# CC_Led_Driver.net
KiCad netlist of a schematic drawn in Altium Designer
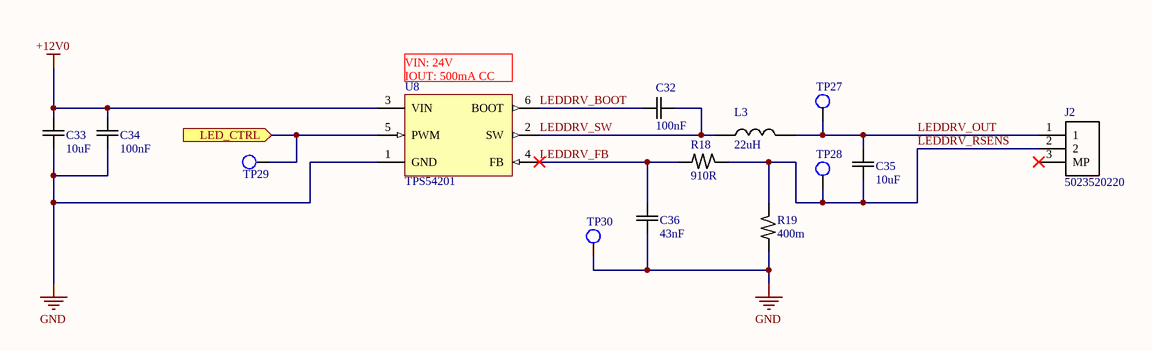
[diagram p0: CC Led Driver.SchDoc]

(export (version "E")
  (design (tool "Eeschema 10.0.6"))
  (components
    (comp (ref "C32")
      (value "100nF")
      (footprint "C0603")
      (description "CAP CER 100nF 50V X7R 0603")
      (fields (field (name "MF") "HRE") (field (name "MP") "CGA0603X7R104K500JT"))
      (libsource (lib "Components") (part "Cap_cer"))
    )
    (comp (ref "C33")
      (value "10uF")
      (footprint "C1206")
      (description "CAP CER 10uF 25V X7R 1206")
      (fields (field (name "MF") "SAMWHA") (field (name "MP") "CS3216X7R106K250NRI"))
      (libsource (lib "Components") (part "Cap_cer"))
    )
    (comp (ref "C34")
      (value "100nF")
      (footprint "C0603")
      (description "CAP CER 100nF 50V X7R 0603")
      (fields (field (name "MF") "HRE") (field (name "MP") "CGA0603X7R104K500JT"))
      (libsource (lib "Components") (part "Cap_cer"))
    )
    (comp (ref "C35")
      (value "10uF")
      (footprint "C1206")
      (description "CAP CER 10uF 25V X7R 1206")
      (fields (field (name "MF") "SAMWHA") (field (name "MP") "CS3216X7R106K250NRI"))
      (libsource (lib "Components") (part "Cap_cer"))
    )
    (comp (ref "C36")
      (value "43nF")
      (footprint "C0603")
      (description "CAP CER 0.047UF 50V X7R 0603")
      (fields (field (name "MF") "Yageo") (field (name "MP") "CC0603JRX7R9BB473"))
      (libsource (lib "Components") (part "Cap_cer"))
    )
    (comp (ref "J2")
      (value "5023520220")
      (footprint "5600200220")
      (fields (field (name "MP") "5600200220") (field (name "MF") "MOLEX"))
      (libsource (lib "Connectors") (part "5023520202"))
    )
    (comp (ref "L3")
      (value "22uH")
      (footprint "Coil 9.7x9.2")
      (description "FIXED IND 22uH 3A 130mΩ SMD,6.6x7.1mm")
      (fields (field (name "MF") "YJYCOIN") (field (name "MP") "YSPI0630A-220M"))
      (libsource (lib "Components") (part "Coil"))
    )
    (comp (ref "R18")
      (value "910R")
      (footprint "R0603")
      (description "RES 910 OHM 1% 1/10W 0603")
      (fields (field (name "MF") "Yageo") (field (name "MP") "RC0603FR-07910RL"))
      (libsource (lib "Components") (part "Res"))
    )
    (comp (ref "R19")
      (value "400m")
      (footprint "R1206")
      (description "400mΩ 1W ±100ppm/℃ Thin Film Resistor ±1% 1206 Chip Resistor - Surface Mount ROHS")
      (fields (field (name "MF") "Milliohm") (field (name "MP") "HoJLRH1206-1W-400mR-1%"))
      (libsource (lib "Components") (part "Res"))
    )
    (comp (ref "TP27")
      (value "TestPoint")
      (footprint "TESTPOINT_SMD_1.27MM")
      (libsource (lib "Components") (part "TestPoint"))
    )
    (comp (ref "TP28")
      (value "TestPoint")
      (footprint "TESTPOINT_SMD_1.27MM")
      (libsource (lib "Components") (part "TestPoint"))
    )
    (comp (ref "TP29")
      (value "TestPoint")
      (footprint "TESTPOINT_SMD_1.27MM")
      (libsource (lib "Components") (part "TestPoint"))
    )
    (comp (ref "TP30")
      (value "TestPoint")
      (footprint "TESTPOINT_SMD_1.27MM")
      (libsource (lib "Components") (part "TestPoint"))
    )
    (comp (ref "U8")
      (value "TPS54201")
      (footprint "SOT23-6")
      (description "IC REG BUCK ADJ 1.5A TSOT23-6")
      (fields (field (name "MP") "TPS54201DDCR") (field (name "MF") "Texas Instruments"))
      (libsource (lib "Components") (part "TPS54201"))
    )
  )
  (nets
    (net (code "1") (name "+12V0") (class "Default")
      (node (ref "C33") (pin "2") (pinfunction "2_2") (pintype "passive"))
      (node (ref "C34") (pin "2") (pinfunction "2_2") (pintype "passive"))
      (node (ref "U8") (pin "3") (pinfunction "VIN_3") (pintype "power_in"))
    )
    (net (code "2") (name "/LEDDRV_BOOT") (class "Default")
      (node (ref "C32") (pin "2") (pinfunction "2_2") (pintype "passive"))
      (node (ref "U8") (pin "6") (pinfunction "BOOT_6") (pintype "output"))
    )
    (net (code "3") (name "/LEDDRV_FB") (class "Default")
      (node (ref "C36") (pin "1") (pinfunction "1_1") (pintype "passive"))
      (node (ref "R18") (pin "1") (pinfunction "1_1") (pintype "passive"))
      (node (ref "U8") (pin "4") (pinfunction "FB_4") (pintype "input"))
    )
    (net (code "4") (name "/LEDDRV_OUT") (class "Default")
      (node (ref "C35") (pin "1") (pinfunction "1_1") (pintype "passive"))
      (node (ref "J2") (pin "1") (pinfunction "1_1") (pintype "passive"))
      (node (ref "L3") (pin "2") (pinfunction "2_2") (pintype "passive"))
      (node (ref "TP27") (pin "1") (pinfunction "1_1") (pintype "passive"))
    )
    (net (code "5") (name "/LEDDRV_RSENS") (class "Default")
      (node (ref "C35") (pin "2") (pinfunction "2_2") (pintype "passive"))
      (node (ref "J2") (pin "2") (pinfunction "2_2") (pintype "passive"))
      (node (ref "R18") (pin "2") (pinfunction "2_2") (pintype "passive"))
      (node (ref "R19") (pin "2") (pinfunction "2_2") (pintype "passive"))
      (node (ref "TP28") (pin "1") (pinfunction "1_1") (pintype "passive"))
    )
    (net (code "6") (name "/LEDDRV_SW") (class "Default")
      (node (ref "C32") (pin "1") (pinfunction "1_1") (pintype "passive"))
      (node (ref "L3") (pin "1") (pinfunction "1_1") (pintype "passive"))
      (node (ref "U8") (pin "2") (pinfunction "SW_2") (pintype "output"))
    )
    (net (code "7") (name "/LED_CTRL") (class "Default")
      (node (ref "TP29") (pin "1") (pinfunction "1_1") (pintype "passive"))
      (node (ref "U8") (pin "5") (pinfunction "PWM_5") (pintype "input"))
    )
    (net (code "8") (name "GND") (class "Default")
      (node (ref "C33") (pin "1") (pinfunction "1_1") (pintype "passive"))
      (node (ref "C34") (pin "1") (pinfunction "1_1") (pintype "passive"))
      (node (ref "C36") (pin "2") (pinfunction "2_2") (pintype "passive"))
      (node (ref "R19") (pin "1") (pinfunction "1_1") (pintype "passive"))
      (node (ref "TP30") (pin "1") (pinfunction "1_1") (pintype "passive"))
      (node (ref "U8") (pin "1") (pinfunction "GND_1") (pintype "power_in"))
    )
    (net (code "9") (name "unconnected-(J2-MP-Pad3)") (class "Default")
      (node (ref "J2") (pin "3") (pinfunction "MP_3") (pintype "passive+no_connect"))
    )
  )
)
